# ProPrj_OPA4377.net
KiCad netlist of a schematic drawn in EasyEDA Pro
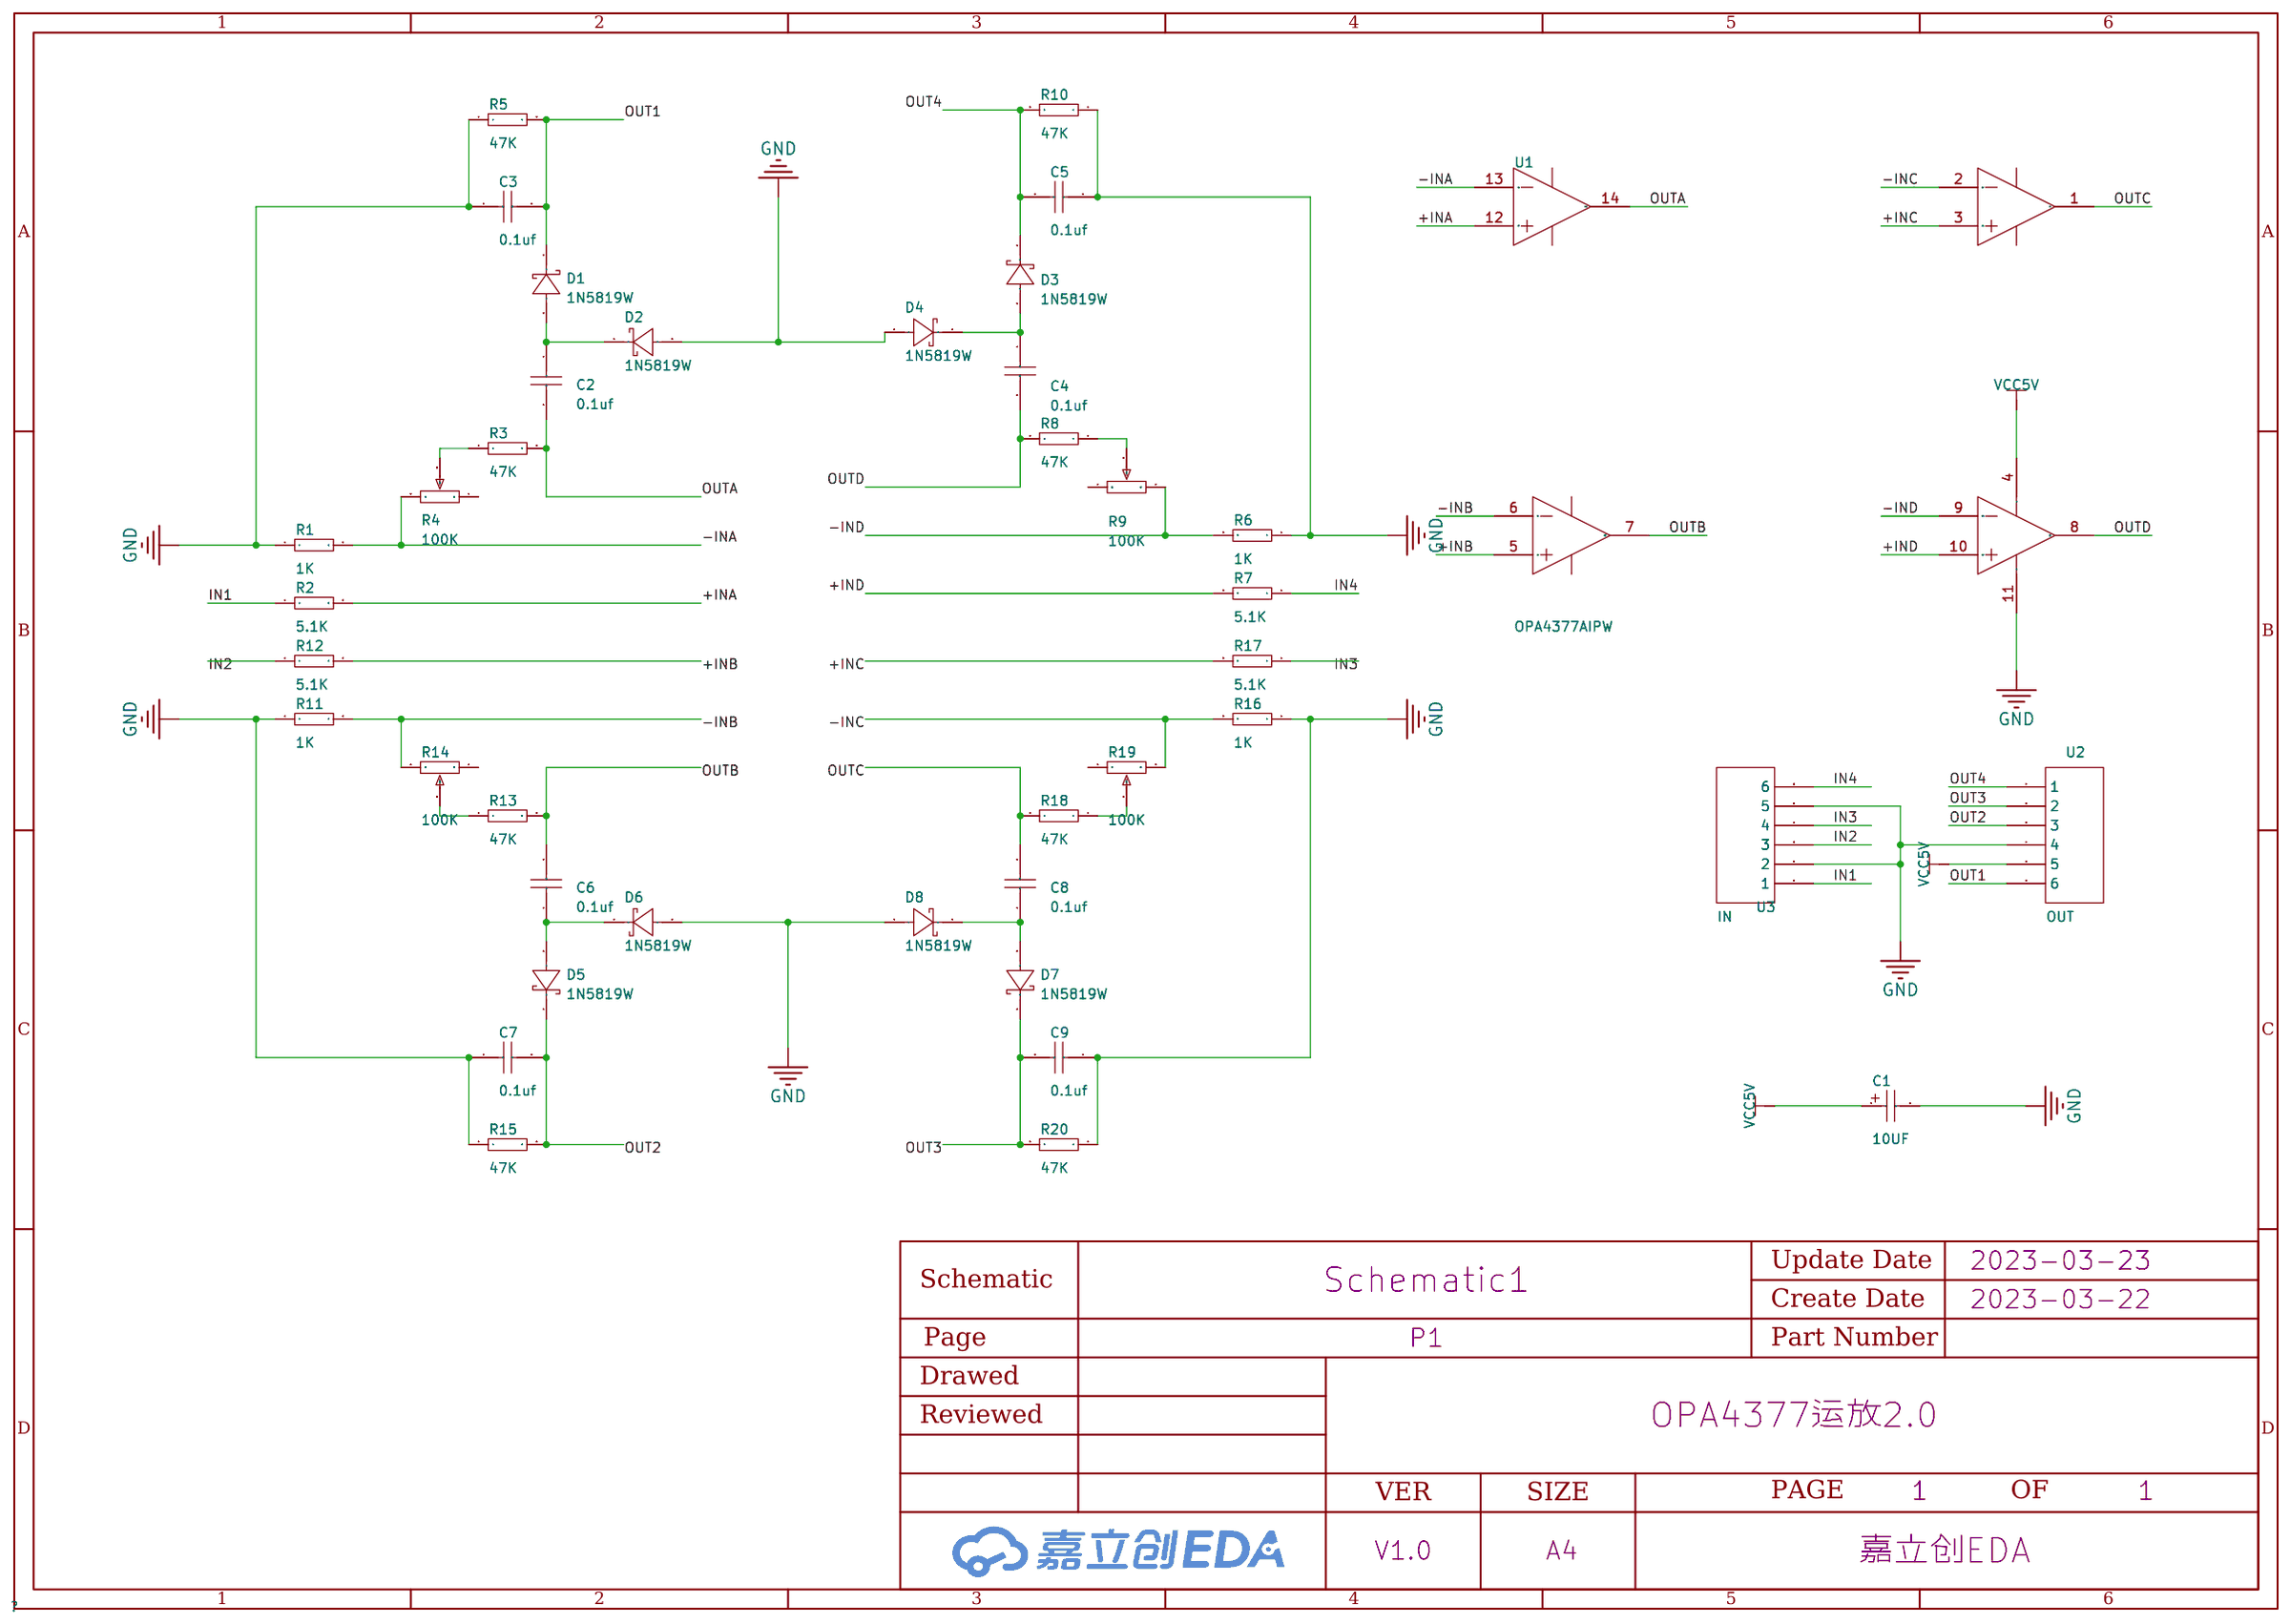
[diagram p0: schematic sheet]

(export (version "E")
  (design (tool "Eeschema 10.0.6"))
  (components
    (comp (ref "C1")
      (value "10UF")
      (footprint "easyedapro:CASE-A_3216")
      (description "容值:1uF;精度:±10%;额定电压:35V;等效串联电阻:7.5Ω@100kHz;工作温度:-55°C~+125°C;")
      (fields (field (name "Manufacturer Part") "TAJA105K035RNJ") (field (name "Manufacturer") "KyoceraAVX"))
      (libsource (lib "easyedapro") (part "TAJA105K035RNJ"))
    )
    (comp (ref "C2")
      (value "1uF")
      (footprint "easyedapro:CAPC1608[0603]S-N")
      (libsource (lib "easyedapro") (part "Cap-Chip_1"))
    )
    (comp (ref "C3")
      (value "1uF")
      (footprint "easyedapro:CAPC1608[0603]S-N")
      (libsource (lib "easyedapro") (part "Cap-Chip_1"))
    )
    (comp (ref "C4")
      (value "1uF")
      (footprint "easyedapro:CAPC1608[0603]S-N")
      (libsource (lib "easyedapro") (part "Cap-Chip_1"))
    )
    (comp (ref "C5")
      (value "1uF")
      (footprint "easyedapro:CAPC1608[0603]S-N")
      (libsource (lib "easyedapro") (part "Cap-Chip_1"))
    )
    (comp (ref "C6")
      (value "1uF")
      (footprint "easyedapro:CAPC1608[0603]S-N")
      (libsource (lib "easyedapro") (part "Cap-Chip_1"))
    )
    (comp (ref "C7")
      (value "1uF")
      (footprint "easyedapro:CAPC1608[0603]S-N")
      (libsource (lib "easyedapro") (part "Cap-Chip_1"))
    )
    (comp (ref "C8")
      (value "1uF")
      (footprint "easyedapro:CAPC1608[0603]S-N")
      (libsource (lib "easyedapro") (part "Cap-Chip_1"))
    )
    (comp (ref "C9")
      (value "1uF")
      (footprint "easyedapro:CAPC1608[0603]S-N")
      (libsource (lib "easyedapro") (part "Cap-Chip_1"))
    )
    (comp (ref "D1")
      (value "1N5819W")
      (footprint "easyedapro:SOD-123_L2.7-W1.6-LS3.7-RD-1")
      (description "二极管配置:-;直流反向耐压(Vr):40V;平均整流电流(Io):1A;正向压降(Vf):900mV@3A;反向电流(Ir):1mA@40V;")
      (fields (field (name "Manufacturer") "TECHPUBLIC(台舟)"))
      (libsource (lib "easyedapro") (part "1N5819W_C2905650"))
    )
    (comp (ref "D2")
      (value "1N5819W")
      (footprint "easyedapro:SOD-123_L2.7-W1.6-LS3.7-RD-1")
      (description "二极管配置:-;直流反向耐压(Vr):40V;平均整流电流(Io):1A;正向压降(Vf):900mV@3A;反向电流(Ir):1mA@40V;")
      (fields (field (name "Manufacturer") "TECHPUBLIC(台舟)"))
      (libsource (lib "easyedapro") (part "1N5819W_C2905650"))
    )
    (comp (ref "D3")
      (value "1N5819W")
      (footprint "easyedapro:SOD-123_L2.7-W1.6-LS3.7-RD-1")
      (description "二极管配置:-;直流反向耐压(Vr):40V;平均整流电流(Io):1A;正向压降(Vf):900mV@3A;反向电流(Ir):1mA@40V;")
      (fields (field (name "Manufacturer") "TECHPUBLIC(台舟)"))
      (libsource (lib "easyedapro") (part "1N5819W_C2905650"))
    )
    (comp (ref "D4")
      (value "1N5819W")
      (footprint "easyedapro:SOD-123_L2.7-W1.6-LS3.7-RD-1")
      (description "二极管配置:-;直流反向耐压(Vr):40V;平均整流电流(Io):1A;正向压降(Vf):900mV@3A;反向电流(Ir):1mA@40V;")
      (fields (field (name "Manufacturer") "TECHPUBLIC(台舟)"))
      (libsource (lib "easyedapro") (part "1N5819W_C2905650"))
    )
    (comp (ref "D5")
      (value "1N5819W")
      (footprint "easyedapro:SOD-123_L2.7-W1.6-LS3.7-RD-1")
      (description "二极管配置:-;直流反向耐压(Vr):40V;平均整流电流(Io):1A;正向压降(Vf):900mV@3A;反向电流(Ir):1mA@40V;")
      (fields (field (name "Manufacturer") "TECHPUBLIC(台舟)"))
      (libsource (lib "easyedapro") (part "1N5819W_C2905650"))
    )
    (comp (ref "D6")
      (value "1N5819W")
      (footprint "easyedapro:SOD-123_L2.7-W1.6-LS3.7-RD-1")
      (description "二极管配置:-;直流反向耐压(Vr):40V;平均整流电流(Io):1A;正向压降(Vf):900mV@3A;反向电流(Ir):1mA@40V;")
      (fields (field (name "Manufacturer") "TECHPUBLIC(台舟)"))
      (libsource (lib "easyedapro") (part "1N5819W_C2905650"))
    )
    (comp (ref "D7")
      (value "1N5819W")
      (footprint "easyedapro:SOD-123_L2.7-W1.6-LS3.7-RD-1")
      (description "二极管配置:-;直流反向耐压(Vr):40V;平均整流电流(Io):1A;正向压降(Vf):900mV@3A;反向电流(Ir):1mA@40V;")
      (fields (field (name "Manufacturer") "TECHPUBLIC(台舟)"))
      (libsource (lib "easyedapro") (part "1N5819W_C2905650"))
    )
    (comp (ref "D8")
      (value "1N5819W")
      (footprint "easyedapro:SOD-123_L2.7-W1.6-LS3.7-RD-1")
      (description "二极管配置:-;直流反向耐压(Vr):40V;平均整流电流(Io):1A;正向压降(Vf):900mV@3A;反向电流(Ir):1mA@40V;")
      (fields (field (name "Manufacturer") "TECHPUBLIC(台舟)"))
      (libsource (lib "easyedapro") (part "1N5819W_C2905650"))
    )
    (comp (ref "R1")
      (value "10R")
      (footprint "easyedapro:RESC1608[0603]S-N")
      (libsource (lib "easyedapro") (part "Res-Chip_9"))
    )
    (comp (ref "R2")
      (value "10R")
      (footprint "easyedapro:RESC1608[0603]S-N")
      (libsource (lib "easyedapro") (part "Res-Chip_9"))
    )
    (comp (ref "R3")
      (value "10R")
      (footprint "easyedapro:RESC1608[0603]S-N")
      (libsource (lib "easyedapro") (part "Res-Chip_9"))
    )
    (comp (ref "R4")
      (value "100K")
      (footprint "easyedapro:RESPOT3296")
      (libsource (lib "easyedapro") (part "Res Adj 3p"))
    )
    (comp (ref "R5")
      (value "10R")
      (footprint "easyedapro:RESC1608[0603]S-N")
      (libsource (lib "easyedapro") (part "Res-Chip_9"))
    )
    (comp (ref "R6")
      (value "10R")
      (footprint "easyedapro:RESC1608[0603]S-N")
      (libsource (lib "easyedapro") (part "Res-Chip_9"))
    )
    (comp (ref "R7")
      (value "10R")
      (footprint "easyedapro:RESC1608[0603]S-N")
      (libsource (lib "easyedapro") (part "Res-Chip_9"))
    )
    (comp (ref "R8")
      (value "10R")
      (footprint "easyedapro:RESC1608[0603]S-N")
      (libsource (lib "easyedapro") (part "Res-Chip_9"))
    )
    (comp (ref "R9")
      (value "100K")
      (footprint "easyedapro:RESPOT3296")
      (libsource (lib "easyedapro") (part "Res Adj 3p"))
    )
    (comp (ref "R10")
      (value "10R")
      (footprint "easyedapro:RESC1608[0603]S-N")
      (libsource (lib "easyedapro") (part "Res-Chip_9"))
    )
    (comp (ref "R11")
      (value "10R")
      (footprint "easyedapro:RESC1608[0603]S-N")
      (libsource (lib "easyedapro") (part "Res-Chip_9"))
    )
    (comp (ref "R12")
      (value "10R")
      (footprint "easyedapro:RESC1608[0603]S-N")
      (libsource (lib "easyedapro") (part "Res-Chip_9"))
    )
    (comp (ref "R13")
      (value "10R")
      (footprint "easyedapro:RESC1608[0603]S-N")
      (libsource (lib "easyedapro") (part "Res-Chip_9"))
    )
    (comp (ref "R14")
      (value "100K")
      (footprint "easyedapro:RESPOT3296")
      (libsource (lib "easyedapro") (part "Res Adj 3p"))
    )
    (comp (ref "R15")
      (value "10R")
      (footprint "easyedapro:RESC1608[0603]S-N")
      (libsource (lib "easyedapro") (part "Res-Chip_9"))
    )
    (comp (ref "R16")
      (value "10R")
      (footprint "easyedapro:RESC1608[0603]S-N")
      (libsource (lib "easyedapro") (part "Res-Chip_9"))
    )
    (comp (ref "R17")
      (value "10R")
      (footprint "easyedapro:RESC1608[0603]S-N")
      (libsource (lib "easyedapro") (part "Res-Chip_9"))
    )
    (comp (ref "R18")
      (value "10R")
      (footprint "easyedapro:RESC1608[0603]S-N")
      (libsource (lib "easyedapro") (part "Res-Chip_9"))
    )
    (comp (ref "R19")
      (value "100K")
      (footprint "easyedapro:RESPOT3296")
      (libsource (lib "easyedapro") (part "Res Adj 3p"))
    )
    (comp (ref "R20")
      (value "10R")
      (footprint "easyedapro:RESC1608[0603]S-N")
      (libsource (lib "easyedapro") (part "Res-Chip_9"))
    )
    (comp (ref "U1")
      (value "OPA4377AIPW")
      (footprint "easyedapro:TSSOP-14_L5.0-W4.4-P0.65-LS6.4-BL")
      (description "四路低成本、低噪声、5.5MHz CMOS 运算放大器 14-TSSOP -40 to 125")
      (fields (field (name "Manufacturer") "TI(德州仪器)"))
      (libsource (lib "easyedapro") (part "OPA4377AIPW"))
    )
    (comp (ref "U2")
      (value "OUT")
      (footprint "easyedapro:HDR1X6")
      (libsource (lib "easyedapro") (part "Header 6"))
    )
    (comp (ref "U3")
      (value "IN")
      (footprint "easyedapro:HDR1X6")
      (libsource (lib "easyedapro") (part "Header 6"))
    )
  )
  (nets
    (net (code "1") (name "/+INA") (class "Default")
      (node (ref "R2") (pin "2") (pinfunction "2_2") (pintype "input"))
      (node (ref "U1") (pin "12") (pinfunction "IN_D+_12") (pintype "input"))
    )
    (net (code "2") (name "/+INB") (class "Default")
      (node (ref "R12") (pin "2") (pinfunction "2_2") (pintype "input"))
      (node (ref "U1") (pin "5") (pinfunction "IN_B+_5") (pintype "input"))
    )
    (net (code "3") (name "/+INC") (class "Default")
      (node (ref "R17") (pin "2") (pinfunction "2_2") (pintype "input"))
      (node (ref "U1") (pin "3") (pinfunction "IN_A+_3") (pintype "input"))
    )
    (net (code "4") (name "/+IND") (class "Default")
      (node (ref "R7") (pin "2") (pinfunction "2_2") (pintype "input"))
      (node (ref "U1") (pin "10") (pinfunction "IN_C+_10") (pintype "input"))
    )
    (net (code "5") (name "/-INA") (class "Default")
      (node (ref "R1") (pin "2") (pinfunction "2_2") (pintype "input"))
      (node (ref "R4") (pin "2") (pinfunction "BOT_2") (pintype "input"))
      (node (ref "U1") (pin "13") (pinfunction "IN_D-_13") (pintype "input"))
    )
    (net (code "6") (name "/-INB") (class "Default")
      (node (ref "R11") (pin "2") (pinfunction "2_2") (pintype "input"))
      (node (ref "R14") (pin "2") (pinfunction "BOT_2") (pintype "input"))
      (node (ref "U1") (pin "6") (pinfunction "IN_B-_6") (pintype "input"))
    )
    (net (code "7") (name "/-INC") (class "Default")
      (node (ref "R16") (pin "2") (pinfunction "2_2") (pintype "input"))
      (node (ref "R19") (pin "2") (pinfunction "BOT_2") (pintype "input"))
      (node (ref "U1") (pin "2") (pinfunction "IN_A-_2") (pintype "input"))
    )
    (net (code "8") (name "/-IND") (class "Default")
      (node (ref "R6") (pin "2") (pinfunction "2_2") (pintype "input"))
      (node (ref "R9") (pin "2") (pinfunction "BOT_2") (pintype "input"))
      (node (ref "U1") (pin "9") (pinfunction "IN_C-_9") (pintype "input"))
    )
    (net (code "9") (name "/IN1") (class "Default")
      (node (ref "R2") (pin "1") (pinfunction "1_1") (pintype "input"))
      (node (ref "U3") (pin "1") (pinfunction "1_1") (pintype "input"))
    )
    (net (code "10") (name "/IN2") (class "Default")
      (node (ref "R12") (pin "1") (pinfunction "1_1") (pintype "input"))
      (node (ref "U3") (pin "3") (pinfunction "3_3") (pintype "input"))
    )
    (net (code "11") (name "/IN3") (class "Default")
      (node (ref "R17") (pin "1") (pinfunction "1_1") (pintype "input"))
      (node (ref "U3") (pin "4") (pinfunction "4_4") (pintype "input"))
    )
    (net (code "12") (name "/IN4") (class "Default")
      (node (ref "R7") (pin "1") (pinfunction "1_1") (pintype "input"))
      (node (ref "U3") (pin "6") (pinfunction "6_6") (pintype "input"))
    )
    (net (code "13") (name "/OUT1") (class "Default")
      (node (ref "C3") (pin "2") (pinfunction "2_2") (pintype "input"))
      (node (ref "D1") (pin "1") (pinfunction "K_1") (pintype "input"))
      (node (ref "R5") (pin "2") (pinfunction "2_2") (pintype "input"))
      (node (ref "U2") (pin "6") (pinfunction "6_6") (pintype "input"))
    )
    (net (code "14") (name "/OUT2") (class "Default")
      (node (ref "C7") (pin "2") (pinfunction "2_2") (pintype "input"))
      (node (ref "D5") (pin "1") (pinfunction "K_1") (pintype "input"))
      (node (ref "R15") (pin "2") (pinfunction "2_2") (pintype "input"))
      (node (ref "U2") (pin "3") (pinfunction "3_3") (pintype "input"))
    )
    (net (code "15") (name "/OUT3") (class "Default")
      (node (ref "C9") (pin "2") (pinfunction "2_2") (pintype "input"))
      (node (ref "D7") (pin "1") (pinfunction "K_1") (pintype "input"))
      (node (ref "R20") (pin "2") (pinfunction "2_2") (pintype "input"))
      (node (ref "U2") (pin "2") (pinfunction "2_2") (pintype "input"))
    )
    (net (code "16") (name "/OUT4") (class "Default")
      (node (ref "C5") (pin "2") (pinfunction "2_2") (pintype "input"))
      (node (ref "D3") (pin "1") (pinfunction "K_1") (pintype "input"))
      (node (ref "R10") (pin "2") (pinfunction "2_2") (pintype "input"))
      (node (ref "U2") (pin "1") (pinfunction "1_1") (pintype "input"))
    )
    (net (code "17") (name "/OUTA") (class "Default")
      (node (ref "C2") (pin "2") (pinfunction "2_2") (pintype "input"))
      (node (ref "R3") (pin "2") (pinfunction "2_2") (pintype "input"))
      (node (ref "U1") (pin "14") (pinfunction "OUT_D_14") (pintype "output"))
    )
    (net (code "18") (name "/OUTB") (class "Default")
      (node (ref "C6") (pin "2") (pinfunction "2_2") (pintype "input"))
      (node (ref "R13") (pin "2") (pinfunction "2_2") (pintype "input"))
      (node (ref "U1") (pin "7") (pinfunction "OUT_B_7") (pintype "output"))
    )
    (net (code "19") (name "/OUTC") (class "Default")
      (node (ref "C8") (pin "2") (pinfunction "2_2") (pintype "input"))
      (node (ref "R18") (pin "2") (pinfunction "2_2") (pintype "input"))
      (node (ref "U1") (pin "1") (pinfunction "OUT_A_1") (pintype "output"))
    )
    (net (code "20") (name "/OUTD") (class "Default")
      (node (ref "C4") (pin "2") (pinfunction "2_2") (pintype "input"))
      (node (ref "R8") (pin "2") (pinfunction "2_2") (pintype "input"))
      (node (ref "U1") (pin "8") (pinfunction "OUT_C_8") (pintype "output"))
    )
    (net (code "21") (name "GND") (class "Default")
      (node (ref "C1") (pin "2") (pinfunction "2_2") (pintype "input"))
      (node (ref "C3") (pin "1") (pinfunction "1_1") (pintype "input"))
      (node (ref "C5") (pin "1") (pinfunction "1_1") (pintype "input"))
      (node (ref "C7") (pin "1") (pinfunction "1_1") (pintype "input"))
      (node (ref "C9") (pin "1") (pinfunction "1_1") (pintype "input"))
      (node (ref "D2") (pin "2") (pinfunction "A_2") (pintype "input"))
      (node (ref "D4") (pin "2") (pinfunction "A_2") (pintype "input"))
      (node (ref "D6") (pin "2") (pinfunction "A_2") (pintype "input"))
      (node (ref "D8") (pin "2") (pinfunction "A_2") (pintype "input"))
      (node (ref "R1") (pin "1") (pinfunction "1_1") (pintype "input"))
      (node (ref "R10") (pin "1") (pinfunction "1_1") (pintype "input"))
      (node (ref "R11") (pin "1") (pinfunction "1_1") (pintype "input"))
      (node (ref "R15") (pin "1") (pinfunction "1_1") (pintype "input"))
      (node (ref "R16") (pin "1") (pinfunction "1_1") (pintype "input"))
      (node (ref "R20") (pin "1") (pinfunction "1_1") (pintype "input"))
      (node (ref "R5") (pin "1") (pinfunction "1_1") (pintype "input"))
      (node (ref "R6") (pin "1") (pinfunction "1_1") (pintype "input"))
      (node (ref "U1") (pin "11") (pinfunction "V-_11") (pintype "input"))
      (node (ref "U2") (pin "4") (pinfunction "4_4") (pintype "input"))
      (node (ref "U3") (pin "2") (pinfunction "2_2") (pintype "input"))
      (node (ref "U3") (pin "5") (pinfunction "5_5") (pintype "input"))
    )
    (net (code "22") (name "Net-(D1-A)") (class "Default")
      (node (ref "C2") (pin "1") (pinfunction "1_1") (pintype "input"))
      (node (ref "D1") (pin "2") (pinfunction "A_2") (pintype "input"))
      (node (ref "D2") (pin "1") (pinfunction "K_1") (pintype "input"))
    )
    (net (code "23") (name "Net-(D3-A)") (class "Default")
      (node (ref "C4") (pin "1") (pinfunction "1_1") (pintype "input"))
      (node (ref "D3") (pin "2") (pinfunction "A_2") (pintype "input"))
      (node (ref "D4") (pin "1") (pinfunction "K_1") (pintype "input"))
    )
    (net (code "24") (name "Net-(D5-A)") (class "Default")
      (node (ref "C6") (pin "1") (pinfunction "1_1") (pintype "input"))
      (node (ref "D5") (pin "2") (pinfunction "A_2") (pintype "input"))
      (node (ref "D6") (pin "1") (pinfunction "K_1") (pintype "input"))
    )
    (net (code "25") (name "Net-(D7-A)") (class "Default")
      (node (ref "C8") (pin "1") (pinfunction "1_1") (pintype "input"))
      (node (ref "D7") (pin "2") (pinfunction "A_2") (pintype "input"))
      (node (ref "D8") (pin "1") (pinfunction "K_1") (pintype "input"))
    )
    (net (code "26") (name "Net-(R3-Pad1)") (class "Default")
      (node (ref "R3") (pin "1") (pinfunction "1_1") (pintype "input"))
      (node (ref "R4") (pin "ADJ") (pinfunction "ADJ_ADJ") (pintype "input"))
    )
    (net (code "27") (name "Net-(R8-Pad1)") (class "Default")
      (node (ref "R8") (pin "1") (pinfunction "1_1") (pintype "input"))
      (node (ref "R9") (pin "ADJ") (pinfunction "ADJ_ADJ") (pintype "input"))
    )
    (net (code "28") (name "Net-(R13-Pad1)") (class "Default")
      (node (ref "R13") (pin "1") (pinfunction "1_1") (pintype "input"))
      (node (ref "R14") (pin "ADJ") (pinfunction "ADJ_ADJ") (pintype "input"))
    )
    (net (code "29") (name "Net-(R18-Pad1)") (class "Default")
      (node (ref "R18") (pin "1") (pinfunction "1_1") (pintype "input"))
      (node (ref "R19") (pin "ADJ") (pinfunction "ADJ_ADJ") (pintype "input"))
    )
    (net (code "30") (name "VCC5V") (class "Default")
      (node (ref "C1") (pin "1") (pinfunction "1_1") (pintype "input"))
      (node (ref "U1") (pin "4") (pinfunction "V+_4") (pintype "input"))
      (node (ref "U2") (pin "5") (pinfunction "5_5") (pintype "input"))
    )
    (net (code "31") (name "unconnected-(R4-TOP-Pad1)") (class "Default")
      (node (ref "R4") (pin "1") (pinfunction "TOP_1") (pintype "input"))
    )
    (net (code "32") (name "unconnected-(R9-TOP-Pad1)") (class "Default")
      (node (ref "R9") (pin "1") (pinfunction "TOP_1") (pintype "input"))
    )
    (net (code "33") (name "unconnected-(R14-TOP-Pad1)") (class "Default")
      (node (ref "R14") (pin "1") (pinfunction "TOP_1") (pintype "input"))
    )
    (net (code "34") (name "unconnected-(R19-TOP-Pad1)") (class "Default")
      (node (ref "R19") (pin "1") (pinfunction "TOP_1") (pintype "input"))
    )
  )
)
